# RFID.net
KiCad netlist of a schematic drawn in Altium Designer
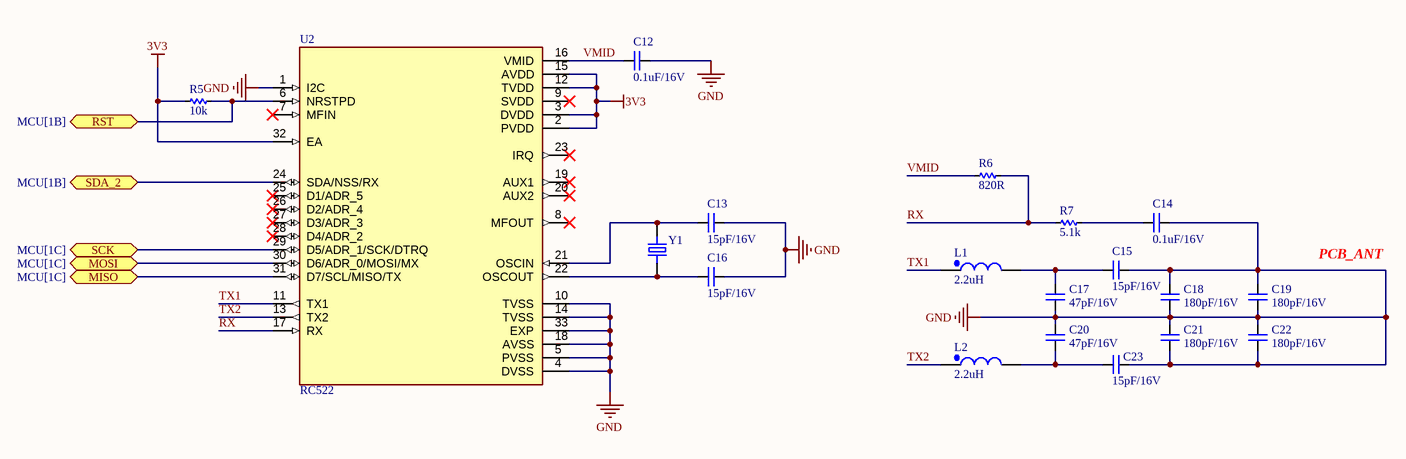
[diagram p0: RFID.SchDoc]

(export (version "E")
  (design (tool "Eeschema 10.0.6"))
  (components
    (comp (ref "C12")
      (value "0.1uF/16V")
      (footprint "CAP_C_1608X80")
      (description "CAP_Chip")
      (libsource (lib "BTL_SCHLIB") (part "CAP_SMD"))
    )
    (comp (ref "C13")
      (value "15pF/16V")
      (footprint "CAP_C_1608X80")
      (description "CAP_Chip")
      (libsource (lib "BTL_SCHLIB") (part "CAP_SMD"))
    )
    (comp (ref "C14")
      (value "0.1uF/16V")
      (footprint "CAP_C_1608X80")
      (description "CAP_Chip")
      (libsource (lib "BTL_SCHLIB") (part "CAP_SMD"))
    )
    (comp (ref "C15")
      (value "15pF/16V")
      (footprint "CAP_C_1608X80")
      (description "CAP_Chip")
      (libsource (lib "BTL_SCHLIB") (part "CAP_SMD"))
    )
    (comp (ref "C16")
      (value "15pF/16V")
      (footprint "CAP_C_1608X80")
      (description "CAP_Chip")
      (libsource (lib "BTL_SCHLIB") (part "CAP_SMD"))
    )
    (comp (ref "C17")
      (value "47pF/16V")
      (footprint "CAP_C_1608X80")
      (description "CAP_Chip")
      (libsource (lib "BTL_SCHLIB") (part "CAP_SMD"))
    )
    (comp (ref "C18")
      (value "180pF/16V")
      (footprint "CAP_C_1608X80")
      (description "CAP_Chip")
      (libsource (lib "BTL_SCHLIB") (part "CAP_SMD"))
    )
    (comp (ref "C19")
      (value "180pF/16V")
      (footprint "CAP_C_1608X80")
      (description "CAP_Chip")
      (libsource (lib "BTL_SCHLIB") (part "CAP_SMD"))
    )
    (comp (ref "C20")
      (value "47pF/16V")
      (footprint "CAP_C_1608X80")
      (description "CAP_Chip")
      (libsource (lib "BTL_SCHLIB") (part "CAP_SMD"))
    )
    (comp (ref "C21")
      (value "180pF/16V")
      (footprint "CAP_C_1608X80")
      (description "CAP_Chip")
      (libsource (lib "BTL_SCHLIB") (part "CAP_SMD"))
    )
    (comp (ref "C22")
      (value "180pF/16V")
      (footprint "CAP_C_1608X80")
      (description "CAP_Chip")
      (libsource (lib "BTL_SCHLIB") (part "CAP_SMD"))
    )
    (comp (ref "C23")
      (value "15pF/16V")
      (footprint "CAP_C_1608X80")
      (description "CAP_Chip")
      (libsource (lib "BTL_SCHLIB") (part "CAP_SMD"))
    )
    (comp (ref "L1") (value "2.2uH") (footprint "IND_C_2012X65") (libsource (lib "BTL_SCHLIB") (part "_IND")))
    (comp (ref "L2") (value "2.2uH") (footprint "IND_C_2012X65") (libsource (lib "BTL_SCHLIB") (part "_IND")))
    (comp (ref "R5")
      (value "10k")
      (footprint "RES_C_1608X60")
      (description "RES")
      (libsource (lib "BTL_SCHLIB") (part "RES_SMD"))
    )
    (comp (ref "R6")
      (value "820R")
      (footprint "RES_C_1608X60")
      (description "RES")
      (libsource (lib "BTL_SCHLIB") (part "RES_SMD"))
    )
    (comp (ref "R7")
      (value "5.1k")
      (footprint "RES_C_1608X60")
      (description "RES")
      (libsource (lib "BTL_SCHLIB") (part "RES_SMD"))
    )
    (comp (ref "U2")
      (value "RC522")
      (footprint "QFN50P500X500X100-33N")
      (description "IC RFID READER 13.56MHZ 32HVQFN")
      (fields (field (name "MF") "NXP USA Inc."))
      (libsource (lib "BTL_SCHLIB") (part "RC522"))
    )
    (comp (ref "Y1")
      (value "C1E-27.120-4-3030-R")
      (footprint "XTAL_C1E-27.120-4-3030-R")
      (description "CRYSTAL 27.1200MHZ 8PF SMD")
      (libsource (lib "BTL_SCHLIB") (part "C1E-27.120-4-3030-R"))
    )
  )
  (nets
    (net (code "1") (name "/MISO") (class "Default")
      (node (ref "U2") (pin "31") (pinfunction "D7/SCL/MISO/TX_31") (pintype "bidirectional"))
    )
    (net (code "2") (name "/MOSI") (class "Default")
      (node (ref "U2") (pin "30") (pinfunction "D6/ADR_0/MOSI/MX_30") (pintype "bidirectional"))
    )
    (net (code "3") (name "/RST") (class "Default")
      (node (ref "R5") (pin "2") (pinfunction "2_2") (pintype "passive"))
      (node (ref "U2") (pin "6") (pinfunction "NRSTPD_6") (pintype "input"))
    )
    (net (code "4") (name "/RX") (class "Default")
      (node (ref "R6") (pin "2") (pinfunction "2_2") (pintype "passive"))
      (node (ref "R7") (pin "1") (pinfunction "1_1") (pintype "passive"))
      (node (ref "U2") (pin "17") (pinfunction "RX_17") (pintype "input"))
    )
    (net (code "5") (name "/SCK") (class "Default")
      (node (ref "U2") (pin "29") (pinfunction "D5/ADR_1/SCK/DTRQ_29") (pintype "bidirectional"))
    )
    (net (code "6") (name "/SDA_2") (class "Default")
      (node (ref "U2") (pin "24") (pinfunction "SDA/NSS/RX_24") (pintype "bidirectional"))
    )
    (net (code "7") (name "/TX1") (class "Default")
      (node (ref "L1") (pin "1") (pinfunction "1_1") (pintype "passive"))
      (node (ref "U2") (pin "11") (pinfunction "TX1_11") (pintype "output"))
    )
    (net (code "8") (name "/TX2") (class "Default")
      (node (ref "L2") (pin "1") (pinfunction "1_1") (pintype "passive"))
      (node (ref "U2") (pin "13") (pinfunction "TX2_13") (pintype "output"))
    )
    (net (code "9") (name "/VMID") (class "Default")
      (node (ref "C12") (pin "1") (pinfunction "1_1") (pintype "passive"))
      (node (ref "R6") (pin "1") (pinfunction "1_1") (pintype "passive"))
      (node (ref "U2") (pin "16") (pinfunction "VMID_16") (pintype "power_in"))
    )
    (net (code "10") (name "3V3") (class "Default")
      (node (ref "R5") (pin "1") (pinfunction "1_1") (pintype "passive"))
      (node (ref "U2") (pin "12") (pinfunction "TVDD_12") (pintype "power_in"))
      (node (ref "U2") (pin "15") (pinfunction "AVDD_15") (pintype "power_in"))
      (node (ref "U2") (pin "2") (pinfunction "PVDD_2") (pintype "power_in"))
      (node (ref "U2") (pin "3") (pinfunction "DVDD_3") (pintype "power_in"))
      (node (ref "U2") (pin "32") (pinfunction "EA_32") (pintype "input"))
    )
    (net (code "11") (name "GND") (class "Default")
      (node (ref "C12") (pin "2") (pinfunction "2_2") (pintype "passive"))
      (node (ref "C13") (pin "2") (pinfunction "2_2") (pintype "passive"))
      (node (ref "C14") (pin "2") (pinfunction "2_2") (pintype "passive"))
      (node (ref "C15") (pin "2") (pinfunction "2_2") (pintype "passive"))
      (node (ref "C16") (pin "2") (pinfunction "2_2") (pintype "passive"))
      (node (ref "C17") (pin "1") (pinfunction "1_1") (pintype "passive"))
      (node (ref "C18") (pin "1") (pinfunction "1_1") (pintype "passive"))
      (node (ref "C18") (pin "2") (pinfunction "2_2") (pintype "passive"))
      (node (ref "C19") (pin "1") (pinfunction "1_1") (pintype "passive"))
      (node (ref "C19") (pin "2") (pinfunction "2_2") (pintype "passive"))
      (node (ref "C20") (pin "2") (pinfunction "2_2") (pintype "passive"))
      (node (ref "C21") (pin "1") (pinfunction "1_1") (pintype "passive"))
      (node (ref "C21") (pin "2") (pinfunction "2_2") (pintype "passive"))
      (node (ref "C22") (pin "1") (pinfunction "1_1") (pintype "passive"))
      (node (ref "C22") (pin "2") (pinfunction "2_2") (pintype "passive"))
      (node (ref "C23") (pin "2") (pinfunction "2_2") (pintype "passive"))
      (node (ref "U2") (pin "1") (pinfunction "I2C_1") (pintype "input"))
      (node (ref "U2") (pin "10") (pinfunction "TVSS_10") (pintype "power_in"))
      (node (ref "U2") (pin "14") (pinfunction "TVSS_14") (pintype "power_in"))
      (node (ref "U2") (pin "18") (pinfunction "AVSS_18") (pintype "power_in"))
      (node (ref "U2") (pin "33") (pinfunction "EXP_33") (pintype "power_in"))
      (node (ref "U2") (pin "4") (pinfunction "DVSS_4") (pintype "power_in"))
      (node (ref "U2") (pin "5") (pinfunction "PVSS_5") (pintype "power_in"))
    )
    (net (code "12") (name "Net-(C14-Pad1)") (class "Default")
      (node (ref "C14") (pin "1") (pinfunction "1_1") (pintype "passive"))
      (node (ref "R7") (pin "2") (pinfunction "2_2") (pintype "passive"))
    )
    (net (code "13") (name "Net-(C15-Pad1)") (class "Default")
      (node (ref "C15") (pin "1") (pinfunction "1_1") (pintype "passive"))
      (node (ref "C17") (pin "2") (pinfunction "2_2") (pintype "passive"))
      (node (ref "L1") (pin "2") (pinfunction "2_2") (pintype "passive"))
    )
    (net (code "14") (name "Net-(C20-Pad1)") (class "Default")
      (node (ref "C20") (pin "1") (pinfunction "1_1") (pintype "passive"))
      (node (ref "C23") (pin "1") (pinfunction "1_1") (pintype "passive"))
      (node (ref "L2") (pin "2") (pinfunction "2_2") (pintype "passive"))
    )
    (net (code "15") (name "Net-(U2-OSCIN)") (class "Default")
      (node (ref "C13") (pin "1") (pinfunction "1_1") (pintype "passive"))
      (node (ref "U2") (pin "21") (pinfunction "OSCIN_21") (pintype "input"))
      (node (ref "Y1") (pin "3") (pinfunction "3_3") (pintype "passive"))
    )
    (net (code "16") (name "Net-(U2-OSCOUT)") (class "Default")
      (node (ref "C16") (pin "1") (pinfunction "1_1") (pintype "passive"))
      (node (ref "U2") (pin "22") (pinfunction "OSCOUT_22") (pintype "output"))
      (node (ref "Y1") (pin "1") (pinfunction "1_1") (pintype "passive"))
    )
    (net (code "17") (name "unconnected-(U2-AUX1-Pad19)") (class "Default")
      (node (ref "U2") (pin "19") (pinfunction "AUX1_19") (pintype "output+no_connect"))
    )
    (net (code "18") (name "unconnected-(U2-AUX2-Pad20)") (class "Default")
      (node (ref "U2") (pin "20") (pinfunction "AUX2_20") (pintype "output+no_connect"))
    )
    (net (code "19") (name "unconnected-(U2-D1{slash}ADR_5-Pad25)") (class "Default")
      (node (ref "U2") (pin "25") (pinfunction "D1/ADR_5_25") (pintype "bidirectional+no_connect"))
    )
    (net (code "20") (name "unconnected-(U2-D2{slash}ADR_4-Pad26)") (class "Default")
      (node (ref "U2") (pin "26") (pinfunction "D2/ADR_4_26") (pintype "bidirectional+no_connect"))
    )
    (net (code "21") (name "unconnected-(U2-D3{slash}ADR_3-Pad27)") (class "Default")
      (node (ref "U2") (pin "27") (pinfunction "D3/ADR_3_27") (pintype "bidirectional+no_connect"))
    )
    (net (code "22") (name "unconnected-(U2-D4{slash}ADR_2-Pad28)") (class "Default")
      (node (ref "U2") (pin "28") (pinfunction "D4/ADR_2_28") (pintype "bidirectional+no_connect"))
    )
    (net (code "23") (name "unconnected-(U2-IRQ-Pad23)") (class "Default")
      (node (ref "U2") (pin "23") (pinfunction "IRQ_23") (pintype "output+no_connect"))
    )
    (net (code "24") (name "unconnected-(U2-MFIN-Pad7)") (class "Default")
      (node (ref "U2") (pin "7") (pinfunction "MFIN_7") (pintype "input+no_connect"))
    )
    (net (code "25") (name "unconnected-(U2-MFOUT-Pad8)") (class "Default")
      (node (ref "U2") (pin "8") (pinfunction "MFOUT_8") (pintype "output+no_connect"))
    )
    (net (code "26") (name "unconnected-(U2-SVDD-Pad9)") (class "Default")
      (node (ref "U2") (pin "9") (pinfunction "SVDD_9") (pintype "power_in+no_connect"))
    )
  )
)
